# DA2_FIN.net
KiCad netlist of a schematic drawn in EasyEDA
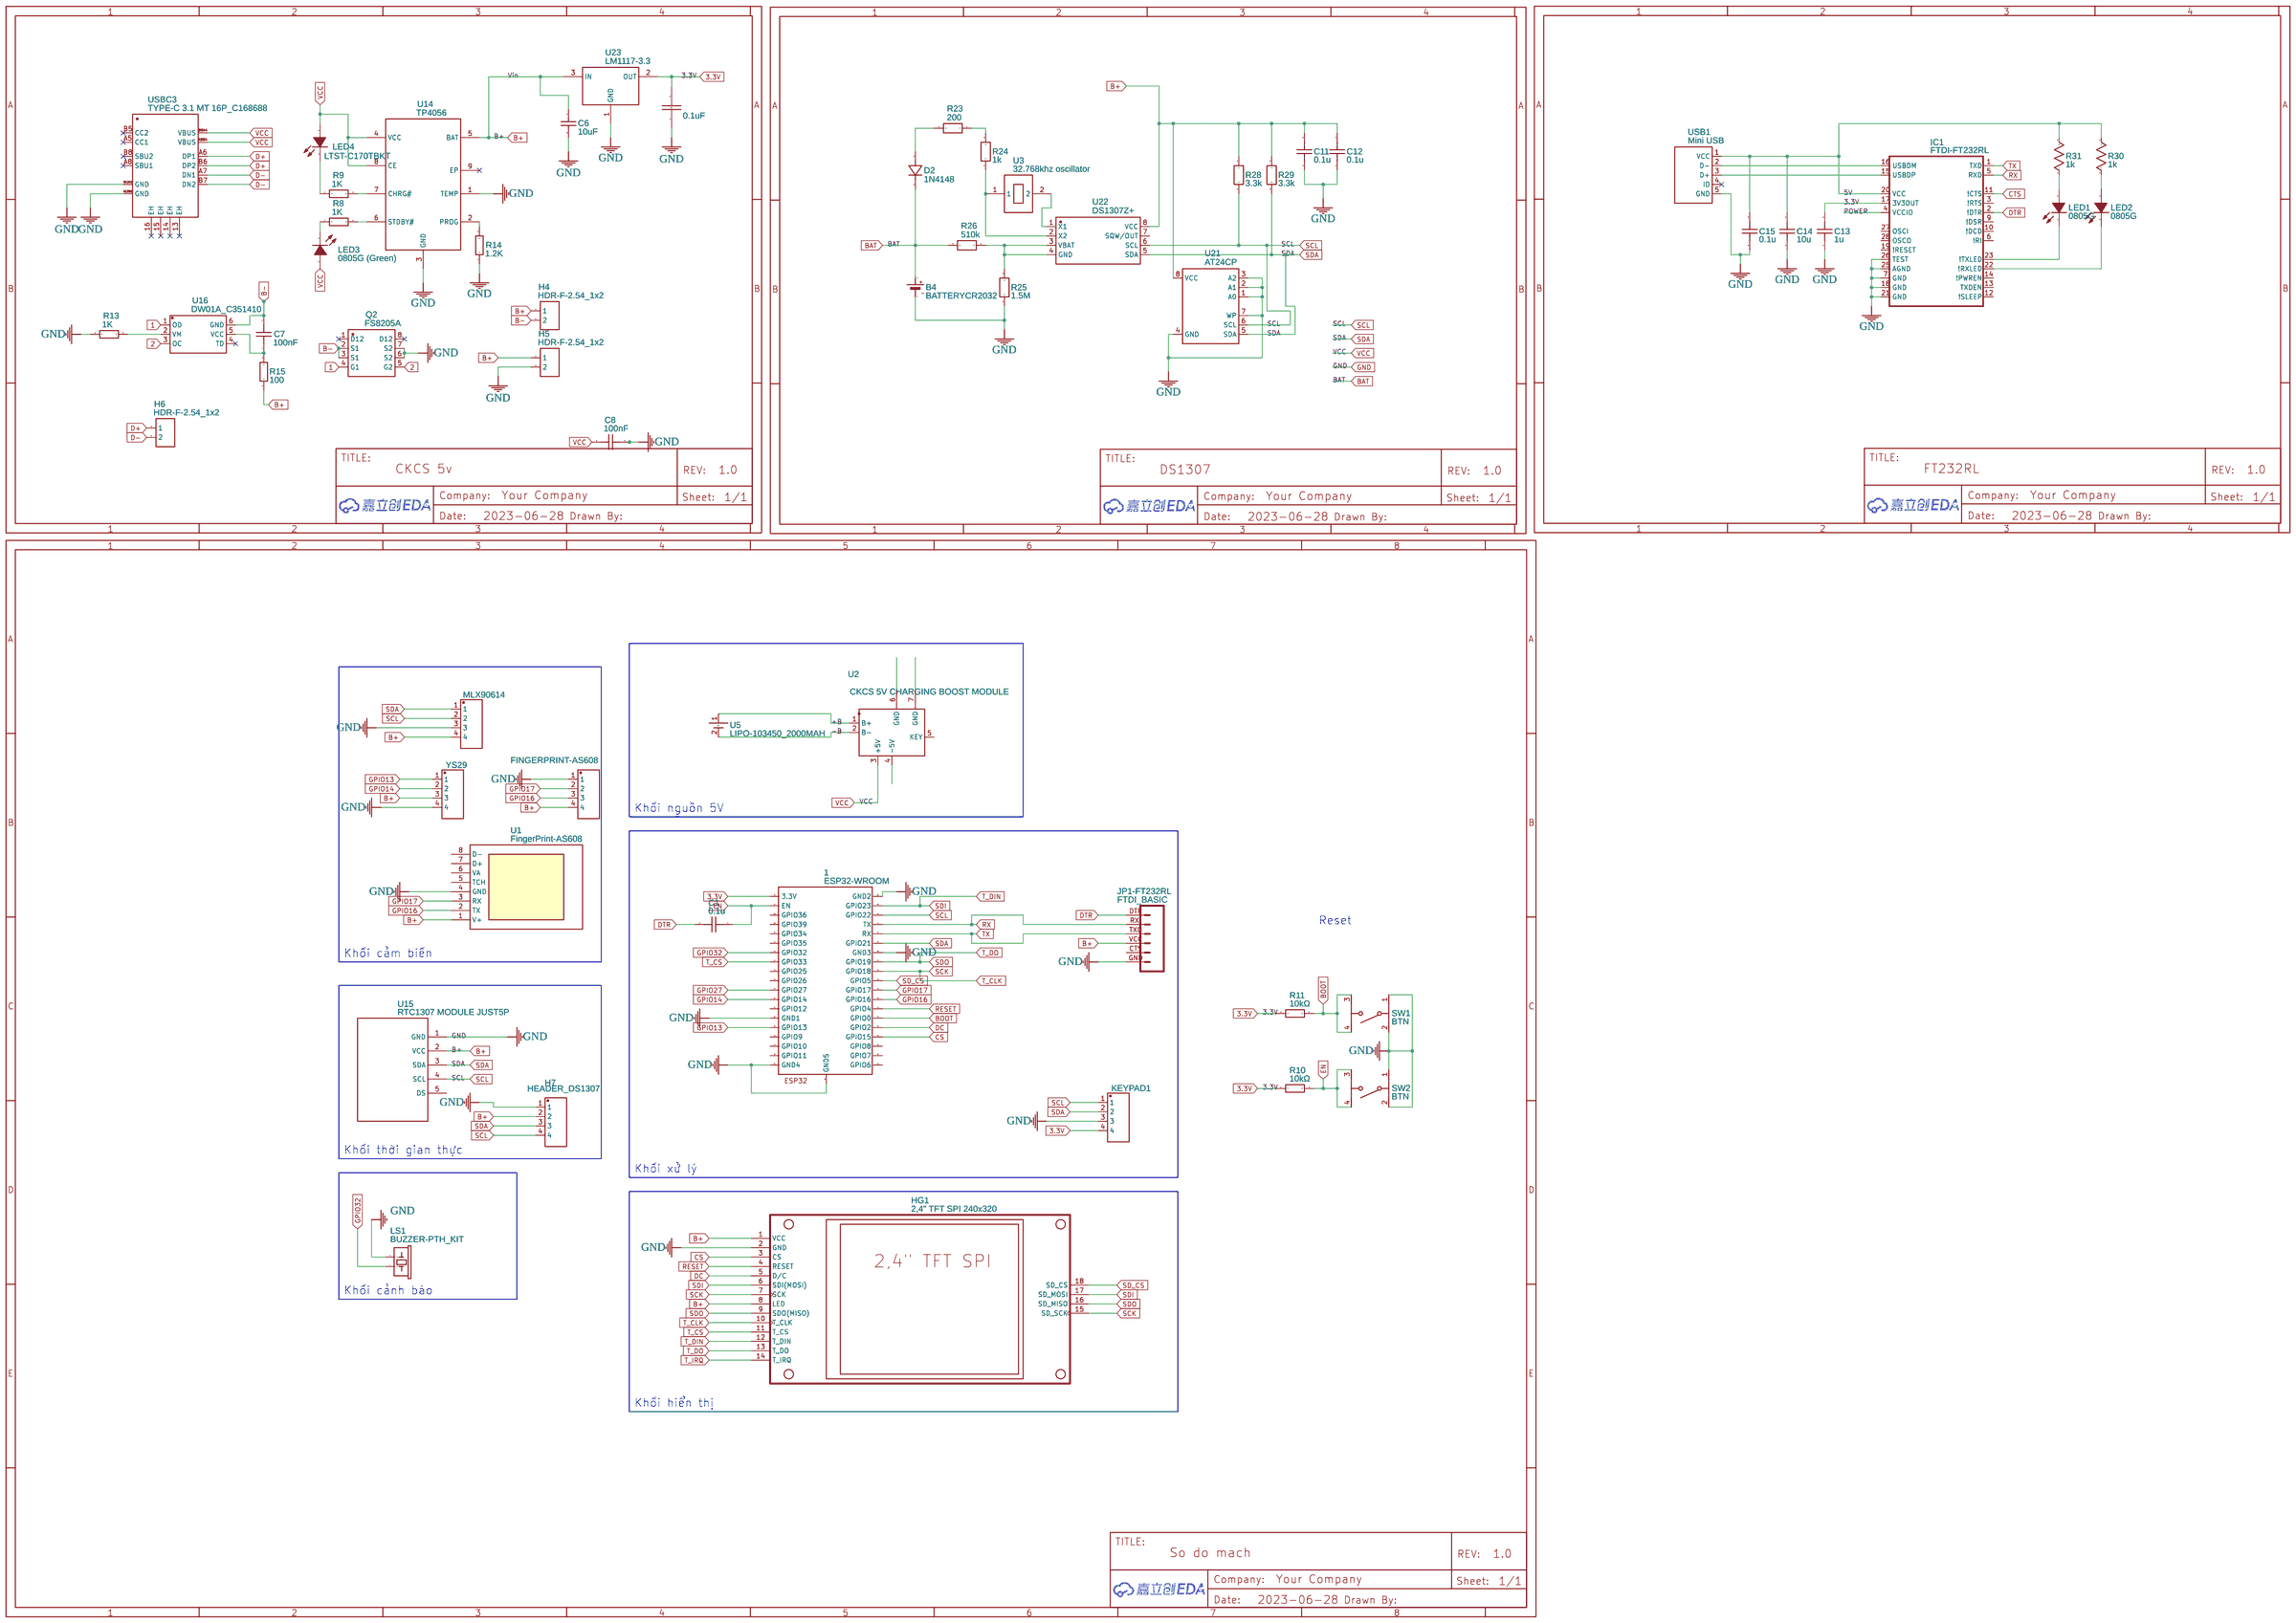
[diagram p0: schematic sheet]

(export (version "E")
  (design (tool "Eeschema 10.0.6"))
  (components
    (comp (ref "1") (value "ESP32-WROOM") (libsource (lib "") (part "ESP32-WROOM")))
    (comp (ref "2") (value "0.1uF") (libsource (lib "") (part "cap 0.1uF 50V 0805")))
    (comp (ref "B4") (value "BATTERYCR2032") (libsource (lib "") (part "BATTERYCR2032")))
    (comp (ref "C1")
      (value "0.1u")
      (fields (field (name "BOM_Manufacturer Part") "?"))
      (libsource (lib "") (part "Cap_1206_US_1"))
    )
    (comp (ref "C6")
      (value "10uF")
      (fields
        (field (name "BOM_Manufacturer Part") "CC0805KKX5R6BB106")
        (field (name "BOM_Supplier Part") "C89832")
      )
      (libsource (lib "") (part "CC0805KKX5R6BB106"))
    )
    (comp (ref "C7")
      (value "100nF")
      (fields
        (field (name "BOM_Manufacturer Part") "C0805B104M500NT")
        (field (name "BOM_Supplier Part") "C515949")
      )
      (libsource (lib "") (part "C0805B104M500NT"))
    )
    (comp (ref "C8")
      (value "100nF")
      (fields
        (field (name "BOM_Manufacturer Part") "C0805B104M500NT")
        (field (name "BOM_Supplier Part") "C515949")
      )
      (libsource (lib "") (part "C0805B104M500NT_1"))
    )
    (comp (ref "C11") (value "0.1u") (libsource (lib "") (part "C_0603_US")))
    (comp (ref "C12") (value "0.1u") (libsource (lib "") (part "C_0603_US")))
    (comp (ref "C13")
      (value "1u")
      (fields (field (name "BOM_Manufacturer Part") "?"))
      (libsource (lib "") (part "Cap_1206_US"))
    )
    (comp (ref "C14")
      (value "10u")
      (fields (field (name "BOM_Manufacturer Part") "?"))
      (libsource (lib "") (part "Cap_1206_US"))
    )
    (comp (ref "C15")
      (value "0.1u")
      (fields (field (name "BOM_Manufacturer Part") "?"))
      (libsource (lib "") (part "Cap_1206_US"))
    )
    (comp (ref "D2")
      (value "1N4148")
      (fields
        (field (name "BOM_Manufacturer Part") "1N4148WSG")
        (field (name "BOM_Supplier Part") "C2904852")
      )
      (libsource (lib "") (part "1N4148WSG_C2904852"))
    )
    (comp (ref "FINGERPRINT-AS608")
      (value "HEADER 1X4P COPY COPY")
      (libsource (lib "") (part "HEADER 1X4P COPY COPY"))
    )
    (comp (ref "H4")
      (value "HDR-F-2.54_1x2")
      (fields (field (name "BOM_Supplier Part") "C49661"))
      (libsource (lib "") (part "HDR-F-2.54_1x2"))
    )
    (comp (ref "H5")
      (value "HDR-F-2.54_1x2")
      (fields (field (name "BOM_Supplier Part") "C49661"))
      (libsource (lib "") (part "HDR-F-2.54_1x2"))
    )
    (comp (ref "H6")
      (value "HDR-F-2.54_1x2")
      (fields (field (name "BOM_Supplier Part") "C49661"))
      (libsource (lib "") (part "HDR-F-2.54_1x2"))
    )
    (comp (ref "H7") (value "HEADER_DS1307") (libsource (lib "") (part "HEADER 1X4P COPY COPY_4")))
    (comp (ref "HG1")
      (value "2,4\" TFT SPI 240x320")
      (fields (field (name "BOM_Manufacturer Part") "2,4\" TFT SPI"))
      (libsource (lib "") (part "2,4&amp;quot; TFT SPI 240x320"))
    )
    (comp (ref "IC1")
      (value "FTDI-FT232RL")
      (fields (field (name "BOM_Manufacturer Part") "?"))
      (libsource (lib "") (part "Unknown_2060_-1485"))
    )
    (comp (ref "JP1-FT232RL")
      (value "FTDI_BASIC")
      (fields (field (name "BOM_Manufacturer Part") "?"))
      (libsource (lib "") (part "Unknown_1215_-730"))
    )
    (comp (ref "KEYPAD1")
      (value "HEADER 1X4P COPY COPY")
      (libsource (lib "") (part "HEADER 1X4P COPY COPY_2"))
    )
    (comp (ref "LED1")
      (value "0805G")
      (fields
        (field (name "BOM_Manufacturer Part") "0805G (Green)")
        (field (name "BOM_Supplier Part") "C2297")
      )
      (libsource (lib "") (part "0805G (Green)_1"))
    )
    (comp (ref "LED2")
      (value "0805G")
      (fields
        (field (name "BOM_Manufacturer Part") "0805G (Green)")
        (field (name "BOM_Supplier Part") "C2297")
      )
      (libsource (lib "") (part "0805G (Green)_1"))
    )
    (comp (ref "LED3")
      (value "0805G (Green)")
      (fields (field (name "BOM_Supplier Part") "C2297"))
      (libsource (lib "") (part "0805G (Green)"))
    )
    (comp (ref "LED4")
      (value "LTST-C170TBKT")
      (fields (field (name "BOM_Supplier Part") "C98222"))
      (libsource (lib "") (part "LTST-C170TBKT"))
    )
    (comp (ref "LS1") (value "BUZZER-PTH_KIT") (libsource (lib "") (part "BUZZER-PTH_KIT")))
    (comp (ref "MLX90614")
      (value "HEADER 1X4P COPY COPY")
      (libsource (lib "") (part "HEADER 1X4P COPY COPY_3"))
    )
    (comp (ref "Q2")
      (value "FS8205A")
      (fields (field (name "BOM_Supplier Part") "C16052"))
      (libsource (lib "") (part "FS8205A"))
    )
    (comp (ref "R8")
      (value "1K")
      (fields
        (field (name "BOM_Manufacturer Part") "AECR0603F1K00K9")
        (field (name "BOM_Supplier Part") "C328340")
      )
      (libsource (lib "") (part "AECR0603F1K00K9"))
    )
    (comp (ref "R9")
      (value "1K")
      (fields
        (field (name "BOM_Manufacturer Part") "AECR0603F1K00K9")
        (field (name "BOM_Supplier Part") "C328340")
      )
      (libsource (lib "") (part "AECR0603F1K00K9"))
    )
    (comp (ref "R10")
      (value "10kΩ")
      (fields
        (field (name "BOM_Manufacturer Part") "PTFR1206B10K0P9")
        (field (name "BOM_Supplier Part") "C351536")
      )
      (libsource (lib "") (part "PTFR1206B10K0P9"))
    )
    (comp (ref "R11")
      (value "10kΩ")
      (fields
        (field (name "BOM_Manufacturer Part") "PTFR1206B10K0P9")
        (field (name "BOM_Supplier Part") "C351536")
      )
      (libsource (lib "") (part "PTFR1206B10K0P9"))
    )
    (comp (ref "R13")
      (value "1K")
      (fields
        (field (name "BOM_Manufacturer Part") "AECR0603F1K00K9")
        (field (name "BOM_Supplier Part") "C328340")
      )
      (libsource (lib "") (part "AECR0603F1K00K9"))
    )
    (comp (ref "R14")
      (value "1.2K")
      (fields
        (field (name "BOM_Manufacturer Part") "RMC06031.2K5%N")
        (field (name "BOM_Supplier Part") "C269681")
      )
      (libsource (lib "") (part "RMC06031.2K5%N"))
    )
    (comp (ref "R15")
      (value "100")
      (fields
        (field (name "BOM_Manufacturer Part") "AECR0603F100RK9")
        (field (name "BOM_Supplier Part") "C328334")
      )
      (libsource (lib "") (part "AECR0603F100RK9"))
    )
    (comp (ref "R23") (value "200") (libsource (lib "") (part "R_0603_EU_1")))
    (comp (ref "R24") (value "1k") (libsource (lib "") (part "R_0603_EU")))
    (comp (ref "R25") (value "1.5M") (libsource (lib "") (part "R_0603_EU")))
    (comp (ref "R26") (value "510k") (libsource (lib "") (part "R_0603_EU_2")))
    (comp (ref "R28") (value "3.3k") (libsource (lib "") (part "R_0603_EU")))
    (comp (ref "R29") (value "3.3k") (libsource (lib "") (part "R_0603_EU")))
    (comp (ref "R30")
      (value "1k")
      (fields (field (name "BOM_Manufacturer Part") "?"))
      (libsource (lib "") (part "Res_1206(1/4W)_US"))
    )
    (comp (ref "R31")
      (value "1k")
      (fields (field (name "BOM_Manufacturer Part") "?"))
      (libsource (lib "") (part "Res_1206(1/4W)_US"))
    )
    (comp (ref "SW1")
      (value "BTN")
      (fields
        (field (name "BOM_Manufacturer Part") "Switch,6*6*6Plastic head,260G, 0.25mm,Straight line")
        (field (name "BOM_Supplier Part") "C71836")
      )
      (libsource (lib "") (part "Button-6x6x6mm"))
    )
    (comp (ref "SW2")
      (value "BTN")
      (fields
        (field (name "BOM_Manufacturer Part") "Switch,6*6*6Plastic head,260G, 0.25mm,Straight line")
        (field (name "BOM_Supplier Part") "C71836")
      )
      (libsource (lib "") (part "Button-6x6x6mm"))
    )
    (comp (ref "U1")
      (value "FingerPrint-AS608")
      (fields (field (name "BOM_Manufacturer Part") "AS-608"))
      (libsource (lib "") (part "FingerPrint-AS608"))
    )
    (comp (ref "U2")
      (value "CKCS 5V CHARGING BOOST MODULE")
      (libsource (lib "") (part "CKCS 5V CHARGING BOOST MODULE"))
    )
    (comp (ref "U3") (value "32.768khz oscillator") (libsource (lib "") (part "32.768khz oscillator")))
    (comp (ref "U5") (value "LIPO-103450_2000MAH") (libsource (lib "") (part "LIPO-103450_2000MAH")))
    (comp (ref "U14")
      (value "TP4056")
      (fields (field (name "BOM_Supplier Part") "C16581"))
      (libsource (lib "") (part "TP4056"))
    )
    (comp (ref "U15") (value "RTC1307 MODULE JUST5P") (libsource (lib "") (part "RTC1307 MODULE JUST5P")))
    (comp (ref "U16")
      (value "DW01A_C351410")
      (fields (field (name "BOM_Manufacturer Part") "DW01A") (field (name "BOM_Supplier Part") "C351410"))
      (libsource (lib "") (part "DW01A_C351410"))
    )
    (comp (ref "U21") (value "AT24CP") (libsource (lib "") (part "AT24CP")))
    (comp (ref "U22")
      (value "DS1307Z+")
      (fields (field (name "BOM_Supplier Part") "C1520446"))
      (libsource (lib "") (part "DS1307Z+"))
    )
    (comp (ref "U23") (value "LM1117-3.3") (libsource (lib "") (part "LM1117-3.3")))
    (comp (ref "USB1") (value "Mini USB") (libsource (lib "") (part "Mini USB")))
    (comp (ref "USBC3")
      (value "TYPE-C 3.1 MT 16P_C168688")
      (fields (field (name "BOM_Supplier Part") "C168688"))
      (libsource (lib "") (part "TYPE-C 3.1 MT 16P_C168688"))
    )
    (comp (ref "YS29") (value "HEADER 1X4P COPY COPY") (libsource (lib "") (part "HEADER 1X4P COPY COPY_1")))
  )
  (nets
    (net (code "1") (name "/+B") (class "Default")
      (node (ref "U2") (pin "1") (pinfunction "B+_1") (pintype "unspecified"))
      (node (ref "U5") (pin "1") (pinfunction "POS_1") (pintype "unspecified"))
    )
    (net (code "2") (name "/-B") (class "Default")
      (node (ref "U2") (pin "2") (pinfunction "B-_2") (pintype "unspecified"))
      (node (ref "U5") (pin "2") (pinfunction "POS_2") (pintype "unspecified"))
    )
    (net (code "3") (name "/5V") (class "Default")
      (node (ref "C14") (pin "2") (pinfunction "2_2") (pintype "unspecified"))
      (node (ref "C15") (pin "2") (pinfunction "2_2") (pintype "unspecified"))
      (node (ref "IC1") (pin "20") (pinfunction "VCC_20") (pintype "bidirectional"))
      (node (ref "R30") (pin "2") (pinfunction "2_2") (pintype "unspecified"))
      (node (ref "R31") (pin "2") (pinfunction "2_2") (pintype "unspecified"))
      (node (ref "USB1") (pin "1") (pinfunction "VCC_1") (pintype "unspecified"))
    )
    (net (code "4") (name "/POWER") (class "Default")
      (node (ref "IC1") (pin "4") (pinfunction "VCCIO_4") (pintype "bidirectional"))
    )
    (net (code "5") (name "1") (class "Default")
      (node (ref "Q2") (pin "4") (pinfunction "G1_4") (pintype "unspecified"))
      (node (ref "U16") (pin "1") (pinfunction "OD_1") (pintype "unspecified"))
    )
    (net (code "6") (name "2") (class "Default")
      (node (ref "Q2") (pin "5") (pinfunction "G2_5") (pintype "unspecified"))
      (node (ref "U16") (pin "3") (pinfunction "OC_3") (pintype "unspecified"))
    )
    (net (code "7") (name "3.3V") (class "Default")
      (node (ref "1") (pin "3V3") (pinfunction "3.3V_3V3") (pintype "bidirectional"))
      (node (ref "2") (pin "2") (pinfunction "2_2") (pintype "unspecified"))
      (node (ref "C13") (pin "2") (pinfunction "2_2") (pintype "unspecified"))
      (node (ref "IC1") (pin "17") (pinfunction "3V3OUT_17") (pintype "bidirectional"))
      (node (ref "KEYPAD1") (pin "4") (pinfunction "4_4") (pintype "unspecified"))
      (node (ref "R10") (pin "1") (pinfunction "1_1") (pintype "unspecified"))
      (node (ref "R11") (pin "1") (pinfunction "1_1") (pintype "unspecified"))
      (node (ref "U23") (pin "2") (pinfunction "OUT_2") (pintype "unspecified"))
    )
    (net (code "8") (name "B+") (class "Default")
      (node (ref "C11") (pin "2") (pinfunction "2_2") (pintype "unspecified"))
      (node (ref "C12") (pin "2") (pinfunction "2_2") (pintype "unspecified"))
      (node (ref "C6") (pin "1") (pinfunction "1_1") (pintype "input"))
      (node (ref "FINGERPRINT-AS608") (pin "4") (pinfunction "4_4") (pintype "unspecified"))
      (node (ref "H4") (pin "1") (pinfunction "1_1") (pintype "input"))
      (node (ref "H5") (pin "1") (pinfunction "1_1") (pintype "input"))
      (node (ref "H7") (pin "2") (pinfunction "2_2") (pintype "unspecified"))
      (node (ref "HG1") (pin "1") (pinfunction "VCC_1") (pintype "passive"))
      (node (ref "HG1") (pin "8") (pinfunction "LED_8") (pintype "passive"))
      (node (ref "JP1-FT232RL") (pin "VCC") (pinfunction "4_VCC") (pintype "unspecified"))
      (node (ref "MLX90614") (pin "4") (pinfunction "4_4") (pintype "unspecified"))
      (node (ref "R15") (pin "1") (pinfunction "1_1") (pintype "unspecified"))
      (node (ref "R28") (pin "2") (pinfunction "2_2") (pintype "unspecified"))
      (node (ref "R29") (pin "2") (pinfunction "2_2") (pintype "unspecified"))
      (node (ref "U1") (pin "1") (pinfunction "V+_1") (pintype "unspecified"))
      (node (ref "U14") (pin "5") (pinfunction "BAT_5") (pintype "unspecified"))
      (node (ref "U15") (pin "2") (pinfunction "VCC_2") (pintype "unspecified"))
      (node (ref "U21") (pin "8") (pinfunction "VCC_8") (pintype "passive"))
      (node (ref "U22") (pin "8") (pinfunction "VCC_8") (pintype "unspecified"))
      (node (ref "U23") (pin "3") (pinfunction "IN_3") (pintype "unspecified"))
      (node (ref "YS29") (pin "3") (pinfunction "3_3") (pintype "unspecified"))
    )
    (net (code "9") (name "B-") (class "Default")
      (node (ref "C7") (pin "2") (pinfunction "2_2") (pintype "unspecified"))
      (node (ref "H4") (pin "2") (pinfunction "2_2") (pintype "input"))
      (node (ref "Q2") (pin "2") (pinfunction "S1_2") (pintype "unspecified"))
      (node (ref "Q2") (pin "3") (pinfunction "S1_3") (pintype "unspecified"))
      (node (ref "U16") (pin "6") (pinfunction "GND_6") (pintype "unspecified"))
    )
    (net (code "10") (name "BAT") (class "Default")
      (node (ref "B4") (pin "+") (pinfunction "+_+") (pintype "bidirectional"))
      (node (ref "D2") (pin "1") (pinfunction "K_1") (pintype "unspecified"))
      (node (ref "R26") (pin "1") (pinfunction "1_1") (pintype "unspecified"))
    )
    (net (code "11") (name "BOOT") (class "Default")
      (node (ref "1") (pin "IO0") (pinfunction "GPIO0_IO0") (pintype "bidirectional"))
      (node (ref "R11") (pin "2") (pinfunction "2_2") (pintype "unspecified"))
      (node (ref "SW1") (pin "3") (pinfunction "3_3") (pintype "unspecified"))
      (node (ref "SW1") (pin "4") (pinfunction "4_4") (pintype "unspecified"))
    )
    (net (code "12") (name "CS") (class "Default")
      (node (ref "1") (pin "IO15") (pinfunction "GPIO15_IO15") (pintype "bidirectional"))
      (node (ref "HG1") (pin "3") (pinfunction "CS_3") (pintype "input"))
    )
    (net (code "13") (name "CTS") (class "Default")
      (node (ref "IC1") (pin "11") (pinfunction "!CTS_11") (pintype "bidirectional"))
    )
    (net (code "14") (name "D+") (class "Default")
      (node (ref "H6") (pin "1") (pinfunction "1_1") (pintype "input"))
      (node (ref "USBC3") (pin "A6") (pinfunction "DP1_A6") (pintype "unspecified"))
      (node (ref "USBC3") (pin "B6") (pinfunction "DP2_B6") (pintype "unspecified"))
    )
    (net (code "15") (name "D-") (class "Default")
      (node (ref "H6") (pin "2") (pinfunction "2_2") (pintype "input"))
      (node (ref "USBC3") (pin "A7") (pinfunction "DN1_A7") (pintype "unspecified"))
      (node (ref "USBC3") (pin "B7") (pinfunction "DN2_B7") (pintype "unspecified"))
    )
    (net (code "16") (name "DC") (class "Default")
      (node (ref "1") (pin "IO2") (pinfunction "GPIO2_IO2") (pintype "bidirectional"))
      (node (ref "HG1") (pin "5") (pinfunction "D/C_5") (pintype "input"))
    )
    (net (code "17") (name "DTR") (class "Default")
      (node (ref "C1") (pin "2") (pinfunction "2_2") (pintype "unspecified"))
      (node (ref "IC1") (pin "2") (pinfunction "!DTR_2") (pintype "bidirectional"))
      (node (ref "JP1-FT232RL") (pin "DTR") (pinfunction "1_DTR") (pintype "unspecified"))
    )
    (net (code "18") (name "EN") (class "Default")
      (node (ref "1") (pin "EN") (pinfunction "EN_EN") (pintype "bidirectional"))
      (node (ref "C1") (pin "1") (pinfunction "1_1") (pintype "unspecified"))
      (node (ref "R10") (pin "2") (pinfunction "2_2") (pintype "unspecified"))
      (node (ref "SW2") (pin "3") (pinfunction "3_3") (pintype "unspecified"))
      (node (ref "SW2") (pin "4") (pinfunction "4_4") (pintype "unspecified"))
    )
    (net (code "19") (name "GND") (class "Default")
      (node (ref "1") (pin "GND1") (pinfunction "GND1_GND1") (pintype "bidirectional"))
      (node (ref "1") (pin "GND2") (pinfunction "GND2_GND2") (pintype "bidirectional"))
      (node (ref "1") (pin "GND3") (pinfunction "GND3_GND3") (pintype "bidirectional"))
      (node (ref "1") (pin "GND4") (pinfunction "GND4_GND4") (pintype "bidirectional"))
      (node (ref "1") (pin "GND5") (pinfunction "GND5_GND5") (pintype "bidirectional"))
      (node (ref "2") (pin "1") (pinfunction "1_1") (pintype "unspecified"))
      (node (ref "B4") (pin "-") (pinfunction "-_-") (pintype "bidirectional"))
      (node (ref "C11") (pin "1") (pinfunction "1_1") (pintype "unspecified"))
      (node (ref "C12") (pin "1") (pinfunction "1_1") (pintype "unspecified"))
      (node (ref "C13") (pin "1") (pinfunction "1_1") (pintype "unspecified"))
      (node (ref "C14") (pin "1") (pinfunction "1_1") (pintype "unspecified"))
      (node (ref "C15") (pin "1") (pinfunction "1_1") (pintype "unspecified"))
      (node (ref "C6") (pin "2") (pinfunction "2_2") (pintype "input"))
      (node (ref "C8") (pin "2") (pinfunction "2_2") (pintype "unspecified"))
      (node (ref "FINGERPRINT-AS608") (pin "1") (pinfunction "1_1") (pintype "unspecified"))
      (node (ref "H5") (pin "2") (pinfunction "2_2") (pintype "input"))
      (node (ref "H7") (pin "1") (pinfunction "1_1") (pintype "unspecified"))
      (node (ref "HG1") (pin "2") (pinfunction "GND_2") (pintype "passive"))
      (node (ref "IC1") (pin "18") (pinfunction "GND_18") (pintype "bidirectional"))
      (node (ref "IC1") (pin "21") (pinfunction "GND_21") (pintype "bidirectional"))
      (node (ref "IC1") (pin "25") (pinfunction "AGND_25") (pintype "bidirectional"))
      (node (ref "IC1") (pin "26") (pinfunction "TEST_26") (pintype "bidirectional"))
      (node (ref "IC1") (pin "7") (pinfunction "GND_7") (pintype "bidirectional"))
      (node (ref "JP1-FT232RL") (pin "GND") (pinfunction "6_GND") (pintype "unspecified"))
      (node (ref "KEYPAD1") (pin "3") (pinfunction "3_3") (pintype "unspecified"))
      (node (ref "LS1") (pin "+") (pinfunction "1_+") (pintype "bidirectional"))
      (node (ref "MLX90614") (pin "3") (pinfunction "3_3") (pintype "unspecified"))
      (node (ref "Q2") (pin "6") (pinfunction "S2_6") (pintype "unspecified"))
      (node (ref "Q2") (pin "7") (pinfunction "S2_7") (pintype "unspecified"))
      (node (ref "R13") (pin "1") (pinfunction "1_1") (pintype "unspecified"))
      (node (ref "R14") (pin "1") (pinfunction "1_1") (pintype "unspecified"))
      (node (ref "R25") (pin "1") (pinfunction "1_1") (pintype "unspecified"))
      (node (ref "SW1") (pin "1") (pinfunction "1_1") (pintype "unspecified"))
      (node (ref "SW1") (pin "2") (pinfunction "2_2") (pintype "unspecified"))
      (node (ref "SW2") (pin "1") (pinfunction "1_1") (pintype "unspecified"))
      (node (ref "SW2") (pin "2") (pinfunction "2_2") (pintype "unspecified"))
      (node (ref "U1") (pin "4") (pinfunction "GND_4") (pintype "unspecified"))
      (node (ref "U14") (pin "1") (pinfunction "TEMP_1") (pintype "unspecified"))
      (node (ref "U14") (pin "3") (pinfunction "GND_3") (pintype "unspecified"))
      (node (ref "U15") (pin "1") (pinfunction "GND_1") (pintype "unspecified"))
      (node (ref "U21") (pin "1") (pinfunction "A0_1") (pintype "input"))
      (node (ref "U21") (pin "2") (pinfunction "A1_2") (pintype "input"))
      (node (ref "U21") (pin "3") (pinfunction "A2_3") (pintype "input"))
      (node (ref "U21") (pin "4") (pinfunction "GND_4") (pintype "passive"))
      (node (ref "U21") (pin "7") (pinfunction "WP_7") (pintype "input"))
      (node (ref "U23") (pin "1") (pinfunction "GND_1") (pintype "unspecified"))
      (node (ref "USB1") (pin "5") (pinfunction "GND_5") (pintype "unspecified"))
      (node (ref "USBC3") (pin "A12B1") (pinfunction "GND_A12B1") (pintype "unspecified"))
      (node (ref "USBC3") (pin "B12A1") (pinfunction "GND_B12A1") (pintype "unspecified"))
      (node (ref "YS29") (pin "4") (pinfunction "4_4") (pintype "unspecified"))
    )
    (net (code "20") (name "GPIO13") (class "Default")
      (node (ref "1") (pin "IO13") (pinfunction "GPIO13_IO13") (pintype "bidirectional"))
      (node (ref "YS29") (pin "1") (pinfunction "1_1") (pintype "unspecified"))
    )
    (net (code "21") (name "GPIO14") (class "Default")
      (node (ref "1") (pin "IO14") (pinfunction "GPIO14_IO14") (pintype "bidirectional"))
      (node (ref "YS29") (pin "2") (pinfunction "2_2") (pintype "unspecified"))
    )
    (net (code "22") (name "GPIO16") (class "Default")
      (node (ref "1") (pin "IO16") (pinfunction "GPIO16_IO16") (pintype "bidirectional"))
      (node (ref "FINGERPRINT-AS608") (pin "3") (pinfunction "3_3") (pintype "unspecified"))
      (node (ref "U1") (pin "2") (pinfunction "TX_2") (pintype "unspecified"))
    )
    (net (code "23") (name "GPIO17") (class "Default")
      (node (ref "1") (pin "IO17") (pinfunction "GPIO17_IO17") (pintype "bidirectional"))
      (node (ref "FINGERPRINT-AS608") (pin "2") (pinfunction "2_2") (pintype "unspecified"))
      (node (ref "U1") (pin "3") (pinfunction "RX_3") (pintype "unspecified"))
    )
    (net (code "24") (name "GPIO27") (class "Default")
      (node (ref "1") (pin "IO27") (pinfunction "GPIO27_IO27") (pintype "bidirectional"))
    )
    (net (code "25") (name "GPIO32") (class "Default")
      (node (ref "1") (pin "IO32") (pinfunction "GPIO32_IO32") (pintype "bidirectional"))
      (node (ref "LS1") (pin "-") (pinfunction "2_-") (pintype "bidirectional"))
    )
    (net (code "26") (name "Net-(D2-A)") (class "Default")
      (node (ref "D2") (pin "2") (pinfunction "A_2") (pintype "unspecified"))
      (node (ref "R23") (pin "2") (pinfunction "2_2") (pintype "unspecified"))
    )
    (net (code "27") (name "Net-(IC1-!RXLED)") (class "Default")
      (node (ref "IC1") (pin "22") (pinfunction "!RXLED_22") (pintype "bidirectional"))
      (node (ref "LED2") (pin "1") (pinfunction "K_1") (pintype "unspecified"))
    )
    (net (code "28") (name "Net-(IC1-!TXLED)") (class "Default")
      (node (ref "IC1") (pin "23") (pinfunction "!TXLED_23") (pintype "bidirectional"))
      (node (ref "LED1") (pin "1") (pinfunction "K_1") (pintype "unspecified"))
    )
    (net (code "29") (name "Net-(IC1-USBDM)") (class "Default")
      (node (ref "IC1") (pin "16") (pinfunction "USBDM_16") (pintype "bidirectional"))
      (node (ref "USB1") (pin "2") (pinfunction "D-_2") (pintype "unspecified"))
    )
    (net (code "30") (name "Net-(IC1-USBDP)") (class "Default")
      (node (ref "IC1") (pin "15") (pinfunction "USBDP_15") (pintype "bidirectional"))
      (node (ref "USB1") (pin "3") (pinfunction "D+_3") (pintype "unspecified"))
    )
    (net (code "31") (name "Net-(LED1-A)") (class "Default")
      (node (ref "LED1") (pin "2") (pinfunction "A_2") (pintype "unspecified"))
      (node (ref "R31") (pin "1") (pinfunction "1_1") (pintype "unspecified"))
    )
    (net (code "32") (name "Net-(LED2-A)") (class "Default")
      (node (ref "LED2") (pin "2") (pinfunction "A_2") (pintype "unspecified"))
      (node (ref "R30") (pin "1") (pinfunction "1_1") (pintype "unspecified"))
    )
    (net (code "33") (name "Net-(LED3-K)") (class "Default")
      (node (ref "LED3") (pin "1") (pinfunction "K_1") (pintype "unspecified"))
      (node (ref "R8") (pin "1") (pinfunction "1_1") (pintype "unspecified"))
    )
    (net (code "34") (name "Net-(LED4-K)") (class "Default")
      (node (ref "LED4") (pin "1") (pinfunction "K_1") (pintype "unspecified"))
      (node (ref "R9") (pin "1") (pinfunction "1_1") (pintype "unspecified"))
    )
    (net (code "35") (name "Net-(R23-Pad1)") (class "Default")
      (node (ref "R23") (pin "1") (pinfunction "1_1") (pintype "unspecified"))
      (node (ref "R24") (pin "2") (pinfunction "2_2") (pintype "unspecified"))
    )
    (net (code "36") (name "Net-(U14-CHRG#)") (class "Default")
      (node (ref "R9") (pin "2") (pinfunction "2_2") (pintype "unspecified"))
      (node (ref "U14") (pin "7") (pinfunction "CHRG#_7") (pintype "unspecified"))
    )
    (net (code "37") (name "Net-(U14-PROG)") (class "Default")
      (node (ref "R14") (pin "2") (pinfunction "2_2") (pintype "unspecified"))
      (node (ref "U14") (pin "2") (pinfunction "PROG_2") (pintype "unspecified"))
    )
    (net (code "38") (name "Net-(U14-STDBY#)") (class "Default")
      (node (ref "R8") (pin "2") (pinfunction "2_2") (pintype "unspecified"))
      (node (ref "U14") (pin "6") (pinfunction "STDBY#_6") (pintype "unspecified"))
    )
    (net (code "39") (name "Net-(U16-VCC)") (class "Default")
      (node (ref "C7") (pin "1") (pinfunction "1_1") (pintype "unspecified"))
      (node (ref "R15") (pin "2") (pinfunction "2_2") (pintype "unspecified"))
      (node (ref "U16") (pin "5") (pinfunction "VCC_5") (pintype "unspecified"))
    )
    (net (code "40") (name "Net-(U16-VM)") (class "Default")
      (node (ref "R13") (pin "2") (pinfunction "2_2") (pintype "unspecified"))
      (node (ref "U16") (pin "2") (pinfunction "VM_2") (pintype "unspecified"))
    )
    (net (code "41") (name "Net-(U22-GND)") (class "Default")
      (node (ref "R25") (pin "2") (pinfunction "2_2") (pintype "unspecified"))
      (node (ref "R26") (pin "2") (pinfunction "2_2") (pintype "unspecified"))
      (node (ref "U22") (pin "3") (pinfunction "VBAT_3") (pintype "unspecified"))
      (node (ref "U22") (pin "4") (pinfunction "GND_4") (pintype "unspecified"))
    )
    (net (code "42") (name "Net-(U22-X1)") (class "Default")
      (node (ref "U22") (pin "1") (pinfunction "X1_1") (pintype "unspecified"))
      (node (ref "U3") (pin "2") (pinfunction "2_2") (pintype "unspecified"))
    )
    (net (code "43") (name "Net-(U22-X2)") (class "Default")
      (node (ref "R24") (pin "1") (pinfunction "1_1") (pintype "unspecified"))
      (node (ref "U22") (pin "2") (pinfunction "X2_2") (pintype "unspecified"))
      (node (ref "U3") (pin "1") (pinfunction "1_1") (pintype "unspecified"))
    )
    (net (code "44") (name "RESET") (class "Default")
      (node (ref "1") (pin "IO4") (pinfunction "GPIO4_IO4") (pintype "bidirectional"))
      (node (ref "HG1") (pin "4") (pinfunction "RESET_4") (pintype "input"))
    )
    (net (code "45") (name "RX") (class "Default")
      (node (ref "1") (pin "TX") (pinfunction "TX_TX") (pintype "bidirectional"))
      (node (ref "IC1") (pin "5") (pinfunction "RXD_5") (pintype "bidirectional"))
      (node (ref "JP1-FT232RL") (pin "RXI") (pinfunction "2_RXI") (pintype "unspecified"))
    )
    (net (code "46") (name "SCK") (class "Default")
      (node (ref "1") (pin "IO18") (pinfunction "GPIO18_IO18") (pintype "bidirectional"))
      (node (ref "HG1") (pin "10") (pinfunction "T_CLK_10") (pintype "input"))
      (node (ref "HG1") (pin "15") (pinfunction "SD_SCK_15") (pintype "input"))
      (node (ref "HG1") (pin "7") (pinfunction "SCK_7") (pintype "input"))
    )
    (net (code "47") (name "SCL") (class "Default")
      (node (ref "1") (pin "IO22") (pinfunction "GPIO22_IO22") (pintype "bidirectional"))
      (node (ref "H7") (pin "4") (pinfunction "4_4") (pintype "unspecified"))
      (node (ref "KEYPAD1") (pin "1") (pinfunction "1_1") (pintype "unspecified"))
      (node (ref "MLX90614") (pin "2") (pinfunction "2_2") (pintype "unspecified"))
      (node (ref "R28") (pin "1") (pinfunction "1_1") (pintype "unspecified"))
      (node (ref "U15") (pin "4") (pinfunction "SCL_4") (pintype "unspecified"))
      (node (ref "U21") (pin "6") (pinfunction "SCL_6") (pintype "unspecified"))
      (node (ref "U22") (pin "6") (pinfunction "SCL_6") (pintype "unspecified"))
    )
    (net (code "48") (name "SDA") (class "Default")
      (node (ref "1") (pin "IO21") (pinfunction "GPIO21_IO21") (pintype "bidirectional"))
      (node (ref "H7") (pin "3") (pinfunction "3_3") (pintype "unspecified"))
      (node (ref "KEYPAD1") (pin "2") (pinfunction "2_2") (pintype "unspecified"))
      (node (ref "MLX90614") (pin "1") (pinfunction "1_1") (pintype "unspecified"))
      (node (ref "R29") (pin "1") (pinfunction "1_1") (pintype "unspecified"))
      (node (ref "U15") (pin "3") (pinfunction "SDA_3") (pintype "unspecified"))
      (node (ref "U21") (pin "5") (pinfunction "SDA_5") (pintype "unspecified"))
      (node (ref "U22") (pin "5") (pinfunction "SDA_5") (pintype "unspecified"))
    )
    (net (code "49") (name "SDI") (class "Default")
      (node (ref "1") (pin "IO23") (pinfunction "GPIO23_IO23") (pintype "bidirectional"))
      (node (ref "HG1") (pin "12") (pinfunction "T_DIN_12") (pintype "input"))
      (node (ref "HG1") (pin "17") (pinfunction "SD_MOSI_17") (pintype "input"))
      (node (ref "HG1") (pin "6") (pinfunction "SDI(MOSI)_6") (pintype "input"))
    )
    (net (code "50") (name "SDO") (class "Default")
      (node (ref "1") (pin "IO19") (pinfunction "GPIO19_IO19") (pintype "bidirectional"))
      (node (ref "HG1") (pin "13") (pinfunction "T_DO_13") (pintype "output"))
      (node (ref "HG1") (pin "16") (pinfunction "SD_MISO_16") (pintype "output"))
      (node (ref "HG1") (pin "9") (pinfunction "SDO(MISO)_9") (pintype "output"))
    )
    (net (code "51") (name "SD_CS") (class "Default")
      (node (ref "1") (pin "IO5") (pinfunction "GPIO5_IO5") (pintype "bidirectional"))
      (node (ref "HG1") (pin "18") (pinfunction "SD_CS_18") (pintype "input"))
    )
    (net (code "52") (name "TX") (class "Default")
      (node (ref "1") (pin "RX") (pinfunction "RX_RX") (pintype "bidirectional"))
      (node (ref "IC1") (pin "1") (pinfunction "TXD_1") (pintype "bidirectional"))
      (node (ref "JP1-FT232RL") (pin "TXO") (pinfunction "3_TXO") (pintype "unspecified"))
    )
    (net (code "53") (name "T_CS") (class "Default")
      (node (ref "1") (pin "IO33") (pinfunction "GPIO33_IO33") (pintype "bidirectional"))
      (node (ref "HG1") (pin "11") (pinfunction "T_CS_11") (pintype "input"))
    )
    (net (code "54") (name "T_IRQ") (class "Default")
      (node (ref "HG1") (pin "14") (pinfunction "T_IRQ_14") (pintype "output"))
    )
    (net (code "55") (name "VCC") (class "Default")
      (node (ref "C8") (pin "1") (pinfunction "1_1") (pintype "unspecified"))
      (node (ref "LED3") (pin "2") (pinfunction "A_2") (pintype "unspecified"))
      (node (ref "LED4") (pin "2") (pinfunction "A_2") (pintype "unspecified"))
      (node (ref "U14") (pin "4") (pinfunction "VCC_4") (pintype "unspecified"))
      (node (ref "U14") (pin "8") (pinfunction "CE_8") (pintype "unspecified"))
      (node (ref "U2") (pin "3") (pinfunction "+5V_3") (pintype "unspecified"))
      (node (ref "USBC3") (pin "A9B4") (pinfunction "VBUS_A9B4") (pintype "unspecified"))
      (node (ref "USBC3") (pin "B9A4") (pinfunction "VBUS_B9A4") (pintype "unspecified"))
    )
    (net (code "56") (name "unconnected-(1-GPIO6-PadCLK)") (class "Default")
      (node (ref "1") (pin "CLK") (pinfunction "GPIO6_CLK") (pintype "bidirectional"))
    )
    (net (code "57") (name "unconnected-(1-GPIO7-PadSD0)") (class "Default")
      (node (ref "1") (pin "SD0") (pinfunction "GPIO7_SD0") (pintype "bidirectional"))
    )
    (net (code "58") (name "unconnected-(1-GPIO8-PadSD1)") (class "Default")
      (node (ref "1") (pin "SD1") (pinfunction "GPIO8_SD1") (pintype "bidirectional"))
    )
    (net (code "59") (name "unconnected-(1-GPIO9-PadSD2)") (class "Default")
      (node (ref "1") (pin "SD2") (pinfunction "GPIO9_SD2") (pintype "bidirectional"))
    )
    (net (code "60") (name "unconnected-(1-GPIO10-PadSD3)") (class "Default")
      (node (ref "1") (pin "SD3") (pinfunction "GPIO10_SD3") (pintype "bidirectional"))
    )
    (net (code "61") (name "unconnected-(1-GPIO11-PadCMD)") (class "Default")
      (node (ref "1") (pin "CMD") (pinfunction "GPIO11_CMD") (pintype "bidirectional"))
    )
    (net (code "62") (name "unconnected-(1-GPIO12-PadIO12)") (class "Default")
      (node (ref "1") (pin "IO12") (pinfunction "GPIO12_IO12") (pintype "bidirectional"))
    )
    (net (code "63") (name "unconnected-(1-GPIO25-PadIO25)") (class "Default")
      (node (ref "1") (pin "IO25") (pinfunction "GPIO25_IO25") (pintype "bidirectional"))
    )
    (net (code "64") (name "unconnected-(1-GPIO26-PadIO26)") (class "Default")
      (node (ref "1") (pin "IO26") (pinfunction "GPIO26_IO26") (pintype "bidirectional"))
    )
    (net (code "65") (name "unconnected-(1-GPIO34-PadIO34)") (class "Default")
      (node (ref "1") (pin "IO34") (pinfunction "GPIO34_IO34") (pintype "bidirectional"))
    )
    (net (code "66") (name "unconnected-(1-GPIO35-PadIO35)") (class "Default")
      (node (ref "1") (pin "IO35") (pinfunction "GPIO35_IO35") (pintype "bidirectional"))
    )
    (net (code "67") (name "unconnected-(1-GPIO36-PadSENSOR_VP)") (class "Default")
      (node (ref "1") (pin "SENSOR_VP") (pinfunction "GPIO36_SENSOR_VP") (pintype "bidirectional"))
    )
    (net (code "68") (name "unconnected-(1-GPIO39-PadSENSOR_VN)") (class "Default")
      (node (ref "1") (pin "SENSOR_VN") (pinfunction "GPIO39_SENSOR_VN") (pintype "bidirectional"))
    )
    (net (code "69") (name "unconnected-(IC1-!DCD-Pad10)") (class "Default")
      (node (ref "IC1") (pin "10") (pinfunction "!DCD_10") (pintype "bidirectional"))
    )
    (net (code "70") (name "unconnected-(IC1-!DSR-Pad9)") (class "Default")
      (node (ref "IC1") (pin "9") (pinfunction "!DSR_9") (pintype "bidirectional"))
    )
    (net (code "71") (name "unconnected-(IC1-!PWREN-Pad14)") (class "Default")
      (node (ref "IC1") (pin "14") (pinfunction "!PWREN_14") (pintype "bidirectional"))
    )
    (net (code "72") (name "unconnected-(IC1-!RESET-Pad19)") (class "Default")
      (node (ref "IC1") (pin "19") (pinfunction "!RESET_19") (pintype "bidirectional"))
    )
    (net (code "73") (name "unconnected-(IC1-!RI-Pad6)") (class "Default")
      (node (ref "IC1") (pin "6") (pinfunction "!RI_6") (pintype "bidirectional"))
    )
    (net (code "74") (name "unconnected-(IC1-!RTS-Pad3)") (class "Default")
      (node (ref "IC1") (pin "3") (pinfunction "!RTS_3") (pintype "bidirectional"))
    )
    (net (code "75") (name "unconnected-(IC1-!SLEEP-Pad12)") (class "Default")
      (node (ref "IC1") (pin "12") (pinfunction "!SLEEP_12") (pintype "bidirectional"))
    )
    (net (code "76") (name "unconnected-(IC1-OSCI-Pad27)") (class "Default")
      (node (ref "IC1") (pin "27") (pinfunction "OSCI_27") (pintype "bidirectional"))
    )
    (net (code "77") (name "unconnected-(IC1-OSCO-Pad28)") (class "Default")
      (node (ref "IC1") (pin "28") (pinfunction "OSCO_28") (pintype "bidirectional"))
    )
    (net (code "78") (name "unconnected-(IC1-TXDEN-Pad13)") (class "Default")
      (node (ref "IC1") (pin "13") (pinfunction "TXDEN_13") (pintype "bidirectional"))
    )
    (net (code "79") (name "unconnected-(JP1-FT232RL-5-PadCTS)") (class "Default")
      (node (ref "JP1-FT232RL") (pin "CTS") (pinfunction "5_CTS") (pintype "unspecified"))
    )
    (net (code "80") (name "unconnected-(Q2-D12-Pad1)") (class "Default")
      (node (ref "Q2") (pin "1") (pinfunction "D12_1") (pintype "unspecified+no_connect"))
    )
    (net (code "81") (name "unconnected-(Q2-D12-Pad8)") (class "Default")
      (node (ref "Q2") (pin "8") (pinfunction "D12_8") (pintype "unspecified+no_connect"))
    )
    (net (code "82") (name "unconnected-(U1-D+-Pad7)") (class "Default")
      (node (ref "U1") (pin "7") (pinfunction "D+_7") (pintype "unspecified"))
    )
    (net (code "83") (name "unconnected-(U1-D--Pad8)") (class "Default")
      (node (ref "U1") (pin "8") (pinfunction "D-_8") (pintype "unspecified"))
    )
    (net (code "84") (name "unconnected-(U1-TCH-Pad5)") (class "Default")
      (node (ref "U1") (pin "5") (pinfunction "TCH_5") (pintype "unspecified"))
    )
    (net (code "85") (name "unconnected-(U1-VA-Pad6)") (class "Default")
      (node (ref "U1") (pin "6") (pinfunction "VA_6") (pintype "unspecified"))
    )
    (net (code "86") (name "unconnected-(U2--5V-Pad4)") (class "Default")
      (node (ref "U2") (pin "4") (pinfunction "-5V_4") (pintype "unspecified"))
    )
    (net (code "87") (name "unconnected-(U2-GND-Pad6)") (class "Default")
      (node (ref "U2") (pin "6") (pinfunction "GND_6") (pintype "unspecified"))
    )
    (net (code "88") (name "unconnected-(U2-GND-Pad7)") (class "Default")
      (node (ref "U2") (pin "7") (pinfunction "GND_7") (pintype "unspecified"))
    )
    (net (code "89") (name "unconnected-(U2-KEY-Pad5)") (class "Default")
      (node (ref "U2") (pin "5") (pinfunction "KEY_5") (pintype "unspecified"))
    )
    (net (code "90") (name "unconnected-(U14-EP-Pad9)") (class "Default")
      (node (ref "U14") (pin "9") (pinfunction "EP_9") (pintype "unspecified+no_connect"))
    )
    (net (code "91") (name "unconnected-(U15-DS-Pad5)") (class "Default")
      (node (ref "U15") (pin "5") (pinfunction "DS_5") (pintype "unspecified"))
    )
    (net (code "92") (name "unconnected-(U16-TD-Pad4)") (class "Default")
      (node (ref "U16") (pin "4") (pinfunction "TD_4") (pintype "unspecified+no_connect"))
    )
    (net (code "93") (name "unconnected-(U22-SQW{slash}OUT-Pad7)") (class "Default")
      (node (ref "U22") (pin "7") (pinfunction "SQW/OUT_7") (pintype "unspecified"))
    )
    (net (code "94") (name "unconnected-(USB1-ID-Pad4)") (class "Default")
      (node (ref "USB1") (pin "4") (pinfunction "ID_4") (pintype "unspecified+no_connect"))
    )
    (net (code "95") (name "unconnected-(USBC3-CC1-PadA5)") (class "Default")
      (node (ref "USBC3") (pin "A5") (pinfunction "CC1_A5") (pintype "unspecified+no_connect"))
    )
    (net (code "96") (name "unconnected-(USBC3-CC2-PadB5)") (class "Default")
      (node (ref "USBC3") (pin "B5") (pinfunction "CC2_B5") (pintype "unspecified+no_connect"))
    )
    (net (code "97") (name "unconnected-(USBC3-EH-Pad13)") (class "Default")
      (node (ref "USBC3") (pin "13") (pinfunction "EH_13") (pintype "unspecified+no_connect"))
    )
    (net (code "98") (name "unconnected-(USBC3-EH-Pad14)") (class "Default")
      (node (ref "USBC3") (pin "14") (pinfunction "EH_14") (pintype "unspecified+no_connect"))
    )
    (net (code "99") (name "unconnected-(USBC3-EH-Pad15)") (class "Default")
      (node (ref "USBC3") (pin "15") (pinfunction "EH_15") (pintype "unspecified+no_connect"))
    )
    (net (code "100") (name "unconnected-(USBC3-EH-Pad16)") (class "Default")
      (node (ref "USBC3") (pin "16") (pinfunction "EH_16") (pintype "unspecified+no_connect"))
    )
    (net (code "101") (name "unconnected-(USBC3-SBU1-PadA8)") (class "Default")
      (node (ref "USBC3") (pin "A8") (pinfunction "SBU1_A8") (pintype "unspecified+no_connect"))
    )
    (net (code "102") (name "unconnected-(USBC3-SBU2-PadB8)") (class "Default")
      (node (ref "USBC3") (pin "B8") (pinfunction "SBU2_B8") (pintype "unspecified+no_connect"))
    )
  )
)
